# Support.net
KiCad netlist of a schematic drawn in Altium Designer
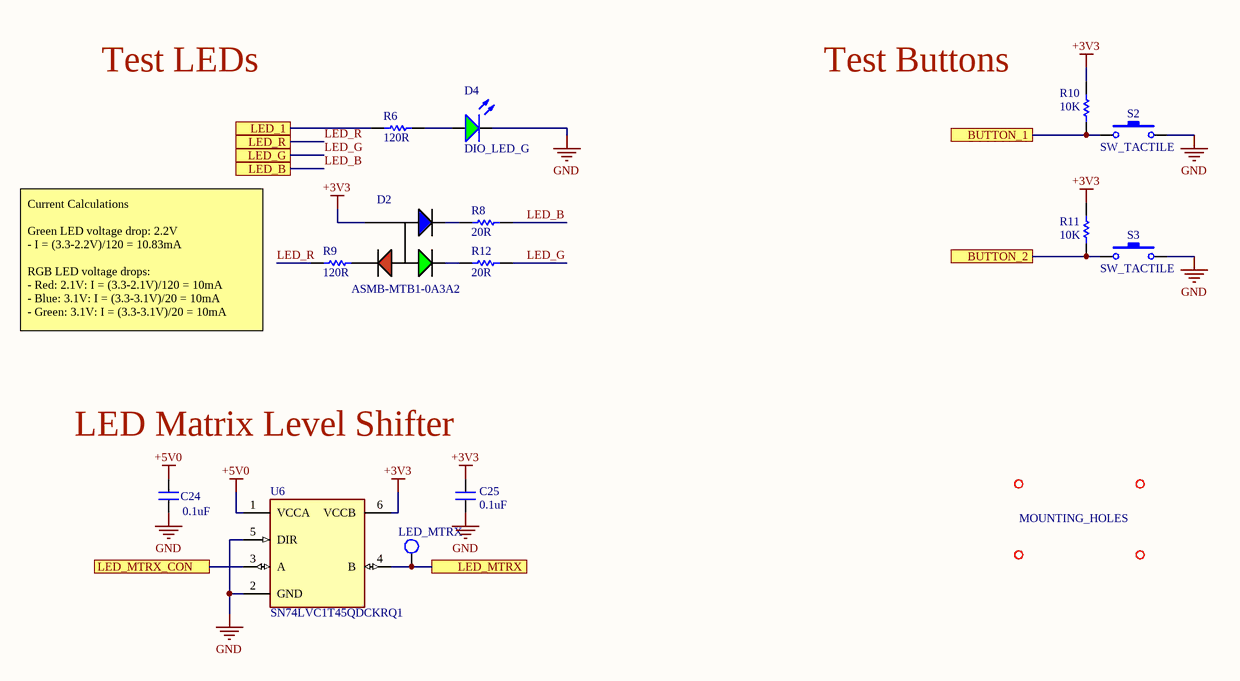
[diagram p0: Support.SchDoc]

(export (version "E")
  (design (tool "Eeschema 10.0.6"))
  (components
    (comp (ref "C24")
      (value "0.1uF")
      (footprint "CAPC0603(1608)55_N")
      (description "CAP CER 0.1UF 16V X7R 0603")
      (fields (field (name "Comment") "CAP_0.1uF_16V_0603"))
      (libsource (lib "UWRT_Schematic_Library_2020") (part "CAP_0.1uF_16V_0603"))
    )
    (comp (ref "C25")
      (value "0.1uF")
      (footprint "CAPC0603(1608)55_N")
      (description "CAP CER 0.1UF 16V X7R 0603")
      (fields (field (name "Comment") "CAP_0.1uF_16V_0603"))
      (libsource (lib "UWRT_Schematic_Library_2020") (part "CAP_0.1uF_16V_0603"))
    )
    (comp (ref "D2")
      (value "LED_RGB")
      (footprint "LED_RGB")
      (description "LED RGB DIFFUSED 4PLCC SMD")
      (fields (field (name "MANUFACTURER PART NUMBER 1") "ASMB-MTB1-0A3A2"))
      (libsource (lib "UWRT_Schematic_Library_2020") (part "LED_RGB"))
    )
    (comp (ref "D4")
      (value "DIO_LED_G")
      (footprint "LED_0805_LINE")
      (description "LED GREEN DIFFUSED 0805 SMD")
      (fields (field (name "MANUFACTURER") "OSRAM") (field (name "MPN") "LG R971-KN-1"))
      (libsource (lib "UWRT_Schematic_Library_2020") (part "DIO_LED_G"))
    )
    (comp (ref "LED_MTRX")
      (value "TESTPOINT_LOOP")
      (footprint "TESTPOINT_LOOP")
      (description "Loop testpoint through-hole pad")
      (libsource (lib "UWRT_Schematic_Library_2020") (part "TESTPOINT_LOOP"))
    )
    (comp (ref "MH1")
      (value "MOUNTING_HOLES")
      (footprint "MOUNTING_HOLE")
      (description "6cm x 6cm")
      (libsource (lib "UWRT_Schematic_Library_2020") (part "MOUNTING_HOLES"))
    )
    (comp (ref "MH2")
      (value "MOUNTING_HOLES")
      (footprint "MOUNTING_HOLE")
      (description "6cm x 6cm")
      (libsource (lib "UWRT_Schematic_Library_2020") (part "MOUNTING_HOLES"))
    )
    (comp (ref "MH3")
      (value "MOUNTING_HOLES")
      (footprint "MOUNTING_HOLE")
      (description "6cm x 6cm")
      (libsource (lib "UWRT_Schematic_Library_2020") (part "MOUNTING_HOLES"))
    )
    (comp (ref "MH4")
      (value "MOUNTING_HOLES")
      (footprint "MOUNTING_HOLE")
      (description "6cm x 6cm")
      (libsource (lib "UWRT_Schematic_Library_2020") (part "MOUNTING_HOLES"))
    )
    (comp (ref "R6")
      (value "120R")
      (footprint "RESC0603(1608)_N")
      (description "RES SMD 120 OHM 5% 1/10W 0603")
      (fields (field (name "MANUFACTURER") "Yageo") (field (name "MPN") "RC0603JR-07120RL"))
      (libsource (lib "UWRT_Schematic_Library_2020") (part "RES_120R_0603"))
    )
    (comp (ref "R8")
      (value "20R")
      (footprint "RESC0603(1608)_N")
      (description "RES SMD 20 OHM 5% 1/10W 0603")
      (fields (field (name "MANUFACTURER") "Yageo") (field (name "MPN") "RC0603JR-0720RL"))
      (libsource (lib "UWRT_Schematic_Library_2020") (part "RES_20R_0603"))
    )
    (comp (ref "R9")
      (value "120R")
      (footprint "RESC0603(1608)_N")
      (description "RES SMD 120 OHM 5% 1/10W 0603")
      (fields (field (name "MANUFACTURER") "Yageo") (field (name "MPN") "RC0603JR-07120RL"))
      (libsource (lib "UWRT_Schematic_Library_2020") (part "RES_120R_0603"))
    )
    (comp (ref "R10")
      (value "10K")
      (footprint "RESC0603(1608)_N")
      (description "RES SMD 10K OHM 5% 1/10W 0603")
      (fields (field (name "MANUFACTURER") "Yageo") (field (name "TOLERANCE") "5%"))
      (libsource (lib "UWRT_Schematic_Library_2020") (part "RES_10K_0603"))
    )
    (comp (ref "R11")
      (value "10K")
      (footprint "RESC0603(1608)_N")
      (description "RES SMD 10K OHM 5% 1/10W 0603")
      (fields (field (name "MANUFACTURER") "Yageo") (field (name "TOLERANCE") "5%"))
      (libsource (lib "UWRT_Schematic_Library_2020") (part "RES_10K_0603"))
    )
    (comp (ref "R12")
      (value "20R")
      (footprint "RESC0603(1608)_N")
      (description "RES SMD 20 OHM 5% 1/10W 0603")
      (fields (field (name "MANUFACTURER") "Yageo") (field (name "MPN") "RC0603JR-0720RL"))
      (libsource (lib "UWRT_Schematic_Library_2020") (part "RES_20R_0603"))
    )
    (comp (ref "S2")
      (value "SW_TACTILE")
      (footprint "B3U-1100P")
      (description "Tactile Switch (Grey)")
      (fields (field (name "MPN") "B3U-1100P") (field (name "MANUFACTURER") "Omron Electronics Inc-EMC Div"))
      (libsource (lib "UWRT_Schematic_Library_2020") (part "SW_TACTILE"))
    )
    (comp (ref "S3")
      (value "SW_TACTILE")
      (footprint "B3U-1100P")
      (description "Tactile Switch (Grey)")
      (fields (field (name "MPN") "B3U-1100P") (field (name "MANUFACTURER") "Omron Electronics Inc-EMC Div"))
      (libsource (lib "UWRT_Schematic_Library_2020") (part "SW_TACTILE"))
    )
    (comp (ref "U6")
      (value "SN74LVC1T45QDCKRQ1")
      (footprint "SOT65P210X110-6N")
      (description "IC BIDIRECTIONAL LEVEL SHIFTER")
      (libsource (lib "UWRT_Schematic_Library_2020") (part "IC_LVL_SHIFTER_TI"))
    )
  )
  (nets
    (net (code "1") (name "+3V3") (class "Default")
      (node (ref "C25") (pin "2") (pinfunction "2_2") (pintype "passive"))
      (node (ref "D2") (pin "4") (pinfunction "9_4") (pintype "passive"))
      (node (ref "R10") (pin "1") (pinfunction "1_1") (pintype "passive"))
      (node (ref "R11") (pin "2") (pinfunction "2_2") (pintype "passive"))
      (node (ref "U6") (pin "6") (pinfunction "VCCB_6") (pintype "passive"))
    )
    (net (code "2") (name "+5V0") (class "Default")
      (node (ref "C24") (pin "2") (pinfunction "2_2") (pintype "passive"))
      (node (ref "U6") (pin "1") (pinfunction "VCCA_1") (pintype "passive"))
    )
    (net (code "3") (name "/BUTTON_1") (class "Default")
      (node (ref "R10") (pin "2") (pinfunction "2_2") (pintype "passive"))
      (node (ref "S2") (pin "1") (pinfunction "1_1") (pintype "passive"))
    )
    (net (code "4") (name "/BUTTON_2") (class "Default")
      (node (ref "R11") (pin "1") (pinfunction "1_1") (pintype "passive"))
      (node (ref "S3") (pin "1") (pinfunction "1_1") (pintype "passive"))
    )
    (net (code "5") (name "/LED_1") (class "Default")
      (node (ref "R6") (pin "1") (pinfunction "1_1") (pintype "passive"))
    )
    (net (code "6") (name "/LED_B") (class "Default")
      (node (ref "R8") (pin "2") (pinfunction "2_2") (pintype "passive"))
    )
    (net (code "7") (name "/LED_G") (class "Default")
      (node (ref "R12") (pin "2") (pinfunction "2_2") (pintype "passive"))
    )
    (net (code "8") (name "/LED_MTRX") (class "Default")
      (node (ref "LED_MTRX") (pin "1") (pintype "passive"))
      (node (ref "U6") (pin "4") (pinfunction "B_4") (pintype "bidirectional"))
    )
    (net (code "9") (name "/LED_MTRX_CON") (class "Default")
      (node (ref "U6") (pin "3") (pinfunction "A_3") (pintype "bidirectional"))
    )
    (net (code "10") (name "/LED_R") (class "Default")
      (node (ref "R9") (pin "1") (pinfunction "1_1") (pintype "passive"))
    )
    (net (code "11") (name "GND") (class "Default")
      (node (ref "C24") (pin "1") (pinfunction "1_1") (pintype "passive"))
      (node (ref "C25") (pin "1") (pinfunction "1_1") (pintype "passive"))
      (node (ref "D4") (pin "2") (pinfunction "K_2") (pintype "passive"))
      (node (ref "S2") (pin "2") (pinfunction "2_2") (pintype "passive"))
      (node (ref "S3") (pin "2") (pinfunction "2_2") (pintype "passive"))
      (node (ref "U6") (pin "2") (pinfunction "GND_2") (pintype "passive"))
      (node (ref "U6") (pin "5") (pinfunction "DIR_5") (pintype "input"))
    )
    (net (code "12") (name "Net-(D2-10)") (class "Default")
      (node (ref "D2") (pin "3") (pinfunction "10_3") (pintype "passive"))
      (node (ref "R8") (pin "1") (pinfunction "1_1") (pintype "passive"))
    )
    (net (code "13") (name "Net-(D2-11)") (class "Default")
      (node (ref "D2") (pin "1") (pinfunction "11_1") (pintype "passive"))
      (node (ref "R9") (pin "2") (pinfunction "2_2") (pintype "passive"))
    )
    (net (code "14") (name "Net-(D2-12)") (class "Default")
      (node (ref "D2") (pin "2") (pinfunction "12_2") (pintype "passive"))
      (node (ref "R12") (pin "1") (pinfunction "1_1") (pintype "passive"))
    )
    (net (code "15") (name "Net-(D4-A)") (class "Default")
      (node (ref "D4") (pin "1") (pinfunction "A_1") (pintype "passive"))
      (node (ref "R6") (pin "2") (pinfunction "2_2") (pintype "passive"))
    )
  )
)
